# KMO_IO_MV2_4.net
KiCad netlist of a schematic drawn in EAGLE
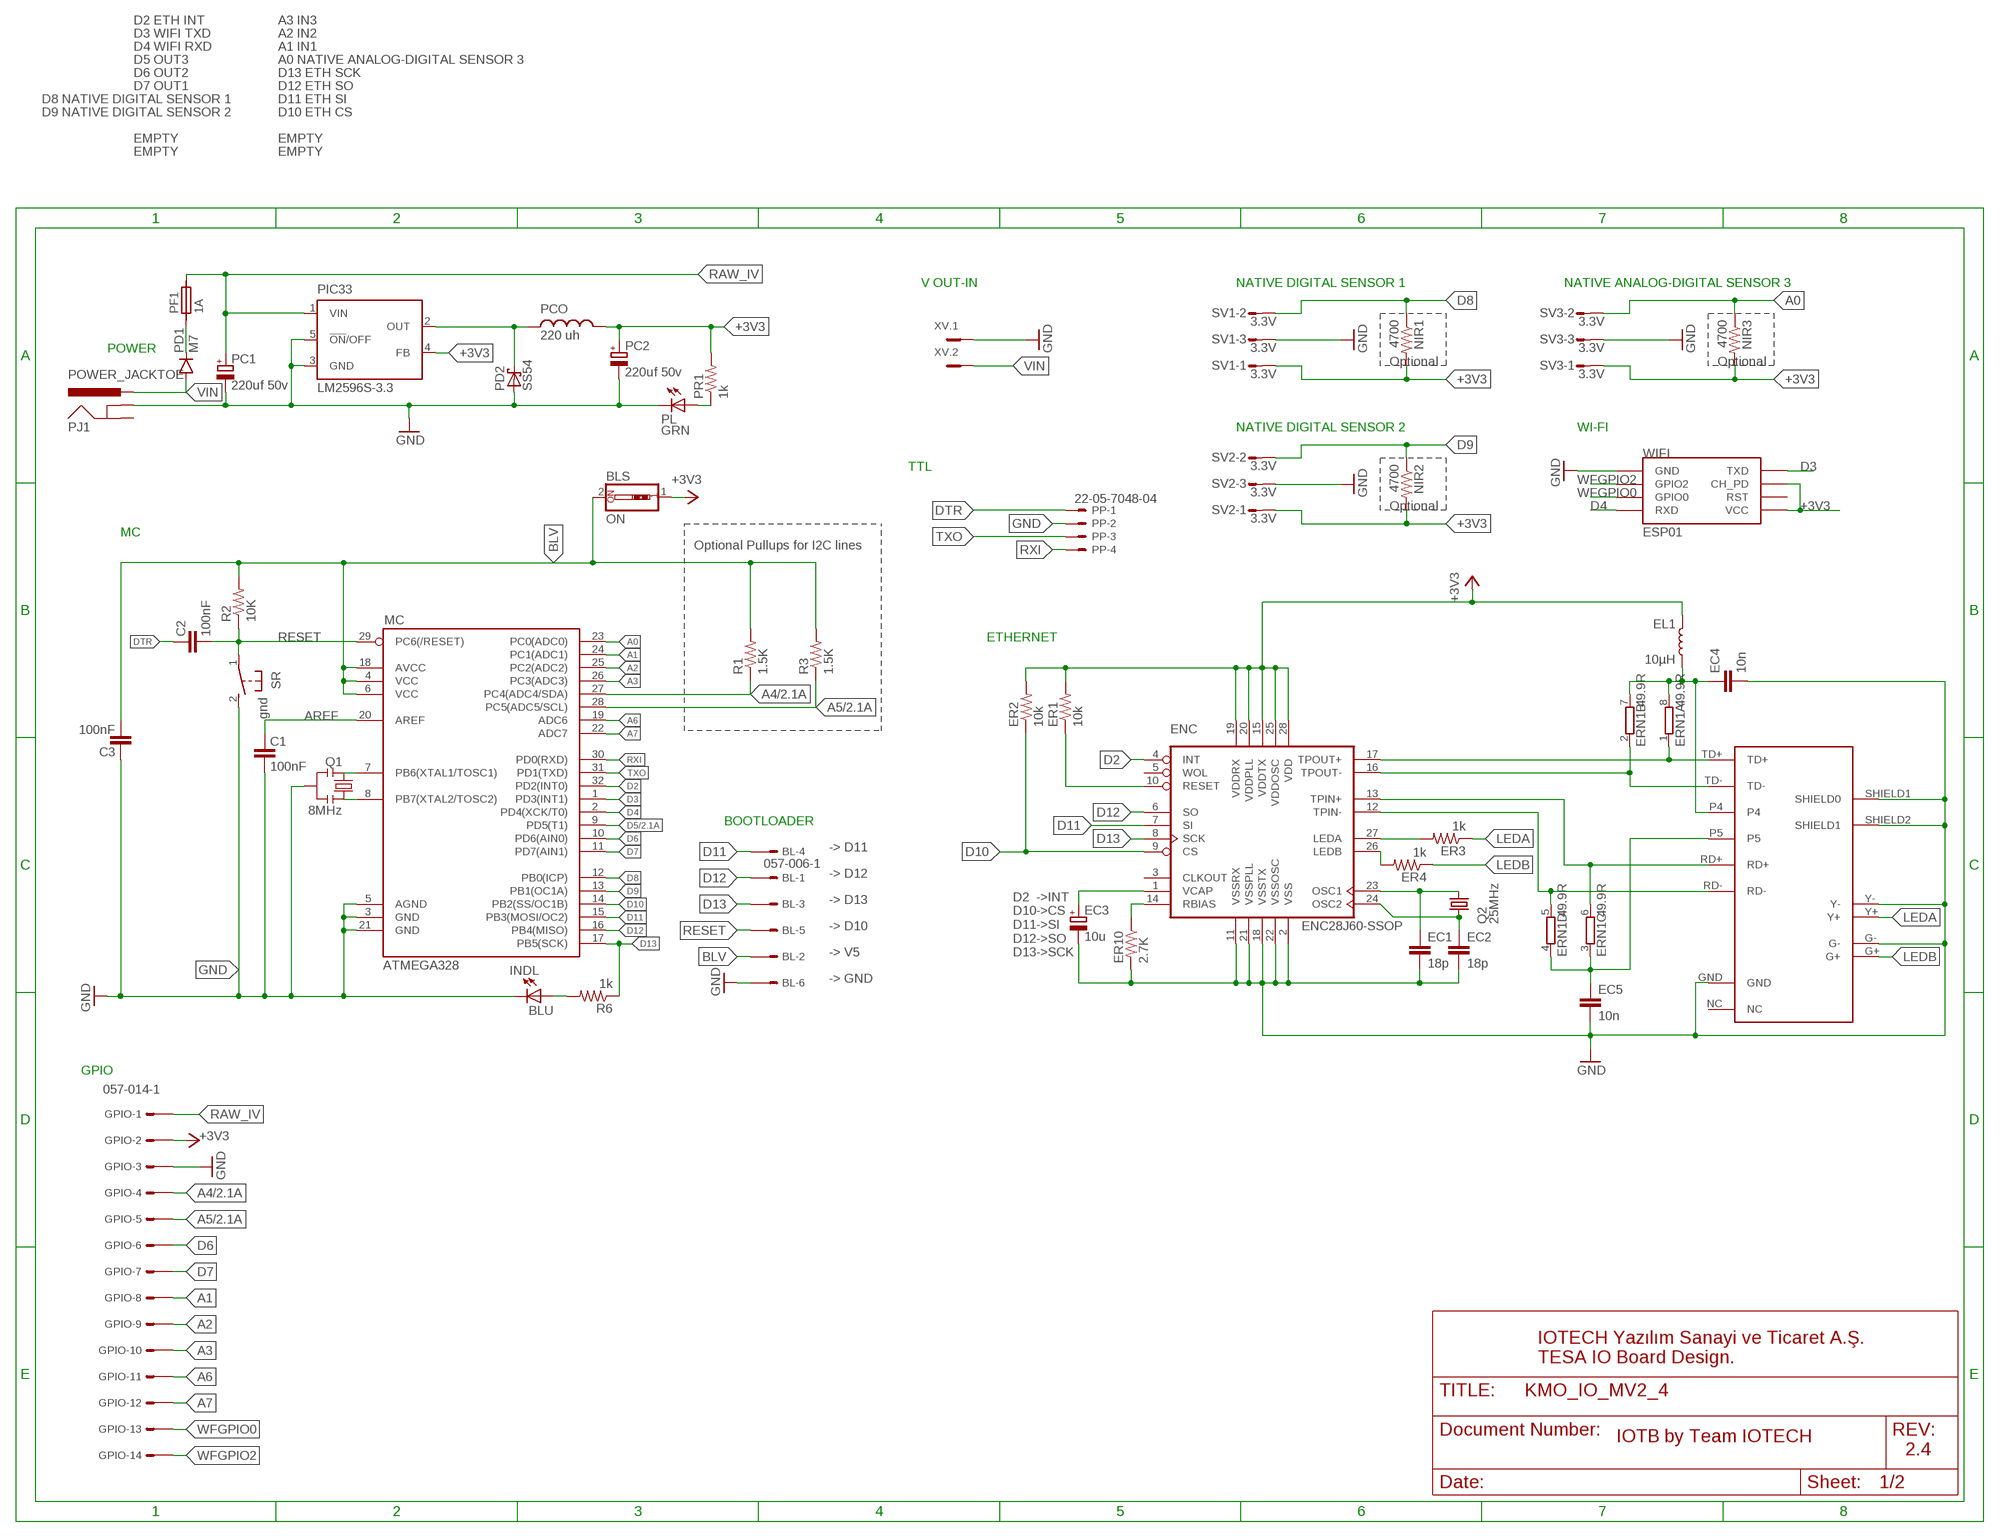
[diagram p0: schematic, sheet 1]
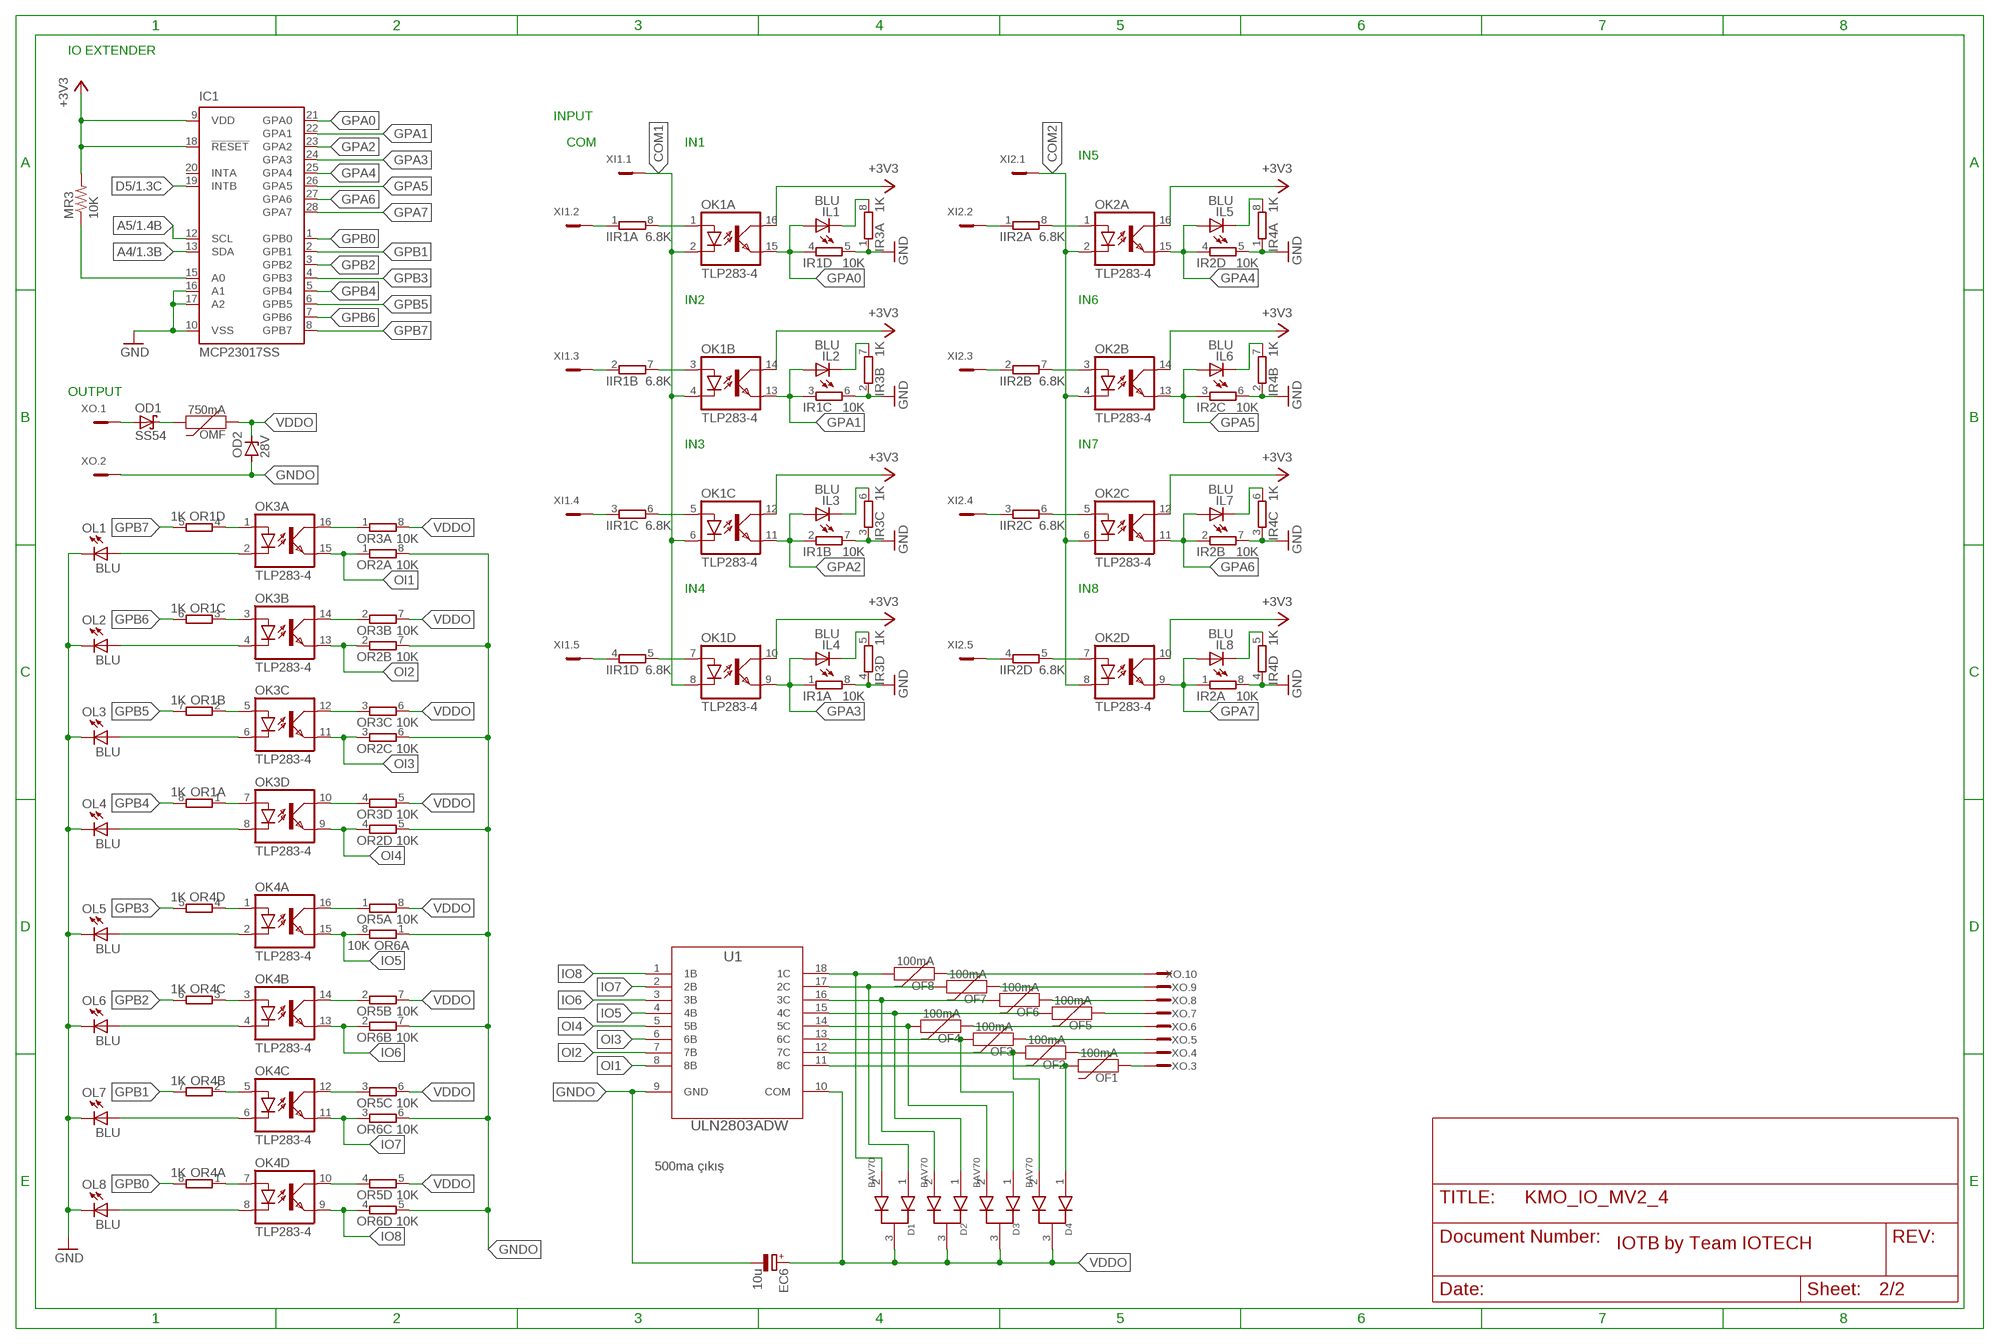
[diagram p1: schematic, sheet 2]

(export (version "E")
  (design (tool "Eeschema 10.0.6"))
  (components
    (comp (ref "BL")
      (value "057-006-1")
      (footprint "eagle-import:057-006-1")
      (libsource (lib "eagle-import") (part "057-006-1"))
    )
    (comp (ref "BLS")
      (value "ON")
      (footprint "eagle-import:EDG-01")
      (libsource (lib "eagle-import") (part "SW_DIP-1"))
    )
    (comp (ref "C1")
      (value "100nF")
      (footprint "eagle-import:0805")
      (libsource (lib "eagle-import") (part "CAP0805"))
    )
    (comp (ref "C2")
      (value "100nF")
      (footprint "eagle-import:0805")
      (libsource (lib "eagle-import") (part "CAP0805"))
    )
    (comp (ref "C3")
      (value "100nF")
      (footprint "eagle-import:0805")
      (libsource (lib "eagle-import") (part "CAP0805"))
    )
    (comp (ref "EC1")
      (value "18p")
      (footprint "eagle-import:0805")
      (libsource (lib "eagle-import") (part "CAP0805"))
    )
    (comp (ref "EC2")
      (value "18p")
      (footprint "eagle-import:0805")
      (libsource (lib "eagle-import") (part "CAP0805"))
    )
    (comp (ref "EC3")
      (value "10u")
      (footprint "eagle-import:CT3216")
      (libsource (lib "eagle-import") (part "CPOL-EUCT3216"))
    )
    (comp (ref "EC4")
      (value "10n")
      (footprint "eagle-import:0805")
      (libsource (lib "eagle-import") (part "CAP0805"))
    )
    (comp (ref "EC5")
      (value "10n")
      (footprint "eagle-import:0805")
      (libsource (lib "eagle-import") (part "CAP0805"))
    )
    (comp (ref "EL1")
      (value "10µH")
      (footprint "eagle-import:0805")
      (libsource (lib "eagle-import") (part "INDUCTOR-0805-3.3UH"))
    )
    (comp (ref "ENC")
      (value "ENC28J60-SSOP")
      (footprint "eagle-import:SSOP28")
      (libsource (lib "eagle-import") (part "ENC28J60-SSOP"))
    )
    (comp (ref "ER1")
      (value "10k")
      (footprint "eagle-import:0805")
      (libsource (lib "eagle-import") (part "RESISTOR0805-RES"))
    )
    (comp (ref "ER2")
      (value "10k")
      (footprint "eagle-import:0805")
      (libsource (lib "eagle-import") (part "RESISTOR0805-RES"))
    )
    (comp (ref "ER3")
      (value "1k")
      (footprint "eagle-import:0805")
      (libsource (lib "eagle-import") (part "RESISTOR0805-RES"))
    )
    (comp (ref "ER4")
      (value "1k")
      (footprint "eagle-import:0805")
      (libsource (lib "eagle-import") (part "RESISTOR0805-RES"))
    )
    (comp (ref "ER10")
      (value "2.7K")
      (footprint "eagle-import:0805")
      (libsource (lib "eagle-import") (part "RESISTOR0805-RES"))
    )
    (comp (ref "ERN1")
      (value "49.9R")
      (footprint "eagle-import:0603-ARV")
      (libsource (lib "eagle-import") (part "4R-N0603-ARV"))
    )
    (comp (ref "GPIO")
      (value "057-014-1")
      (footprint "eagle-import:057-014-1")
      (libsource (lib "eagle-import") (part "057-014-1"))
    )
    (comp (ref "INDL")
      (value "BLU")
      (footprint "eagle-import:CHIP-LED0805")
      (libsource (lib "eagle-import") (part "LEDCHIP-LED0805"))
    )
    (comp (ref "MC")
      (value "ATMEGA328")
      (footprint "eagle-import:TQFP32-08")
      (libsource (lib "eagle-import") (part "ATMEGA168"))
    )
    (comp (ref "NIR1")
      (value "4700")
      (footprint "eagle-import:0805")
      (libsource (lib "eagle-import") (part "RESISTOR0805-RES"))
    )
    (comp (ref "NIR2")
      (value "4700")
      (footprint "eagle-import:0805")
      (libsource (lib "eagle-import") (part "RESISTOR0805-RES"))
    )
    (comp (ref "NIR3")
      (value "4700")
      (footprint "eagle-import:0805")
      (libsource (lib "eagle-import") (part "RESISTOR0805-RES"))
    )
    (comp (ref "PC1")
      (value "220uf 50v")
      (footprint "eagle-import:140CLH-1010")
      (libsource (lib "eagle-import") (part "CPOL-EU140CLH-1010"))
    )
    (comp (ref "PC2")
      (value "220uf 50v")
      (footprint "eagle-import:140CLH-1010")
      (libsource (lib "eagle-import") (part "CPOL-EU140CLH-1010"))
    )
    (comp (ref "PCO")
      (value "220 uh")
      (footprint "eagle-import:MSS1260")
      (libsource (lib "eagle-import") (part "MSS1260"))
    )
    (comp (ref "PD1")
      (value "M7")
      (footprint "eagle-import:SMA-DIODE")
      (libsource (lib "eagle-import") (part "DIODESMA"))
    )
    (comp (ref "PD2")
      (value "SS54")
      (footprint "eagle-import:SMB")
      (libsource (lib "eagle-import") (part "SCHOTTKY-DIODESMD"))
    )
    (comp (ref "PF1")
      (value "1A")
      (footprint "eagle-import:1820")
      (libsource (lib "eagle-import") (part "SIBA194600"))
    )
    (comp (ref "PIC33")
      (value "LM2596S-3.3")
      (footprint "eagle-import:TO263-5")
      (fields
        (field (name "MF") "NATIONAL SEMICONDUCTOR")
        (field (name "MPN") "LM2596S-ADJ/NOPB")
        (field (name "SPICEPREFIX") "X")
      )
      (libsource (lib "eagle-import") (part "LM2596S"))
    )
    (comp (ref "PJ1")
      (value "POWER_JACKTOE")
      (footprint "eagle-import:POWER_JACK_SMD_OVERPASTE_TOE")
      (libsource (lib "eagle-import") (part "POWER_JACKTOE"))
    )
    (comp (ref "PL")
      (value "GRN")
      (footprint "eagle-import:CHIP-LED0805")
      (libsource (lib "eagle-import") (part "LEDCHIP-LED0805"))
    )
    (comp (ref "PP")
      (value "22-05-7048-04")
      (footprint "eagle-import:7395-04")
      (fields (field (name "MF") "MOLEX"))
      (libsource (lib "eagle-import") (part "22-?-0405-7048"))
    )
    (comp (ref "PR1")
      (value "1k")
      (footprint "eagle-import:0805")
      (libsource (lib "eagle-import") (part "RESISTOR0805-RES"))
    )
    (comp (ref "Q1")
      (value "8MHz")
      (footprint "eagle-import:RESONATOR-SMD-1_1")
      (libsource (lib "eagle-import") (part "RESONATOR1{colon}1"))
    )
    (comp (ref "Q2")
      (value "25MHz")
      (footprint "eagle-import:5.0X3.2_2")
      (libsource (lib "eagle-import") (part "KX-9B"))
    )
    (comp (ref "R1")
      (value "1.5K")
      (footprint "eagle-import:0805")
      (libsource (lib "eagle-import") (part "RESISTOR0805-RES"))
    )
    (comp (ref "R2")
      (value "10K")
      (footprint "eagle-import:0805")
      (libsource (lib "eagle-import") (part "RESISTOR0805-RES"))
    )
    (comp (ref "R3")
      (value "1.5K")
      (footprint "eagle-import:0805")
      (libsource (lib "eagle-import") (part "RESISTOR0805-RES"))
    )
    (comp (ref "R6")
      (value "1k")
      (footprint "eagle-import:0805")
      (libsource (lib "eagle-import") (part "RESISTOR0805-RES"))
    )
    (comp (ref "SR")
      (value "gnd")
      (footprint "eagle-import:B3F-31XX")
      (fields (field (name "MPN") "B3F-3100"))
      (libsource (lib "eagle-import") (part "31-XX"))
    )
    (comp (ref "SV1")
      (value "3.3V")
      (footprint "eagle-import:S03P")
      (libsource (lib "eagle-import") (part "S03P"))
    )
    (comp (ref "SV2")
      (value "3.3V")
      (footprint "eagle-import:S03P")
      (libsource (lib "eagle-import") (part "S03P"))
    )
    (comp (ref "SV3")
      (value "3.3V")
      (footprint "eagle-import:S03P")
      (libsource (lib "eagle-import") (part "S03P"))
    )
    (comp (ref "U$2")
      (value "HR911105A")
      (footprint "eagle-import:RJ45")
      (libsource (lib "eagle-import") (part "HR911105A"))
    )
    (comp (ref "WIFI")
      (value "ESP01")
      (footprint "eagle-import:ESP01")
      (libsource (lib "eagle-import") (part "ESP01"))
    )
    (comp (ref "XV")
      (value "MC2")
      (footprint "eagle-import:MC2")
      (libsource (lib "eagle-import") (part "MC2"))
    )
    (comp (ref "D1")
      (value "BAV70")
      (footprint "eagle-import:SOT-23-3")
      (fields (field (name "MF") "Multicomp") (field (name "MP") "BAV70+"))
      (libsource (lib "eagle-import") (part "BAV70"))
    )
    (comp (ref "D2")
      (value "BAV70")
      (footprint "eagle-import:SOT-23-3")
      (fields (field (name "MF") "Multicomp") (field (name "MP") "BAV70+"))
      (libsource (lib "eagle-import") (part "BAV70"))
    )
    (comp (ref "D3")
      (value "BAV70")
      (footprint "eagle-import:SOT-23-3")
      (fields (field (name "MF") "Multicomp") (field (name "MP") "BAV70+"))
      (libsource (lib "eagle-import") (part "BAV70"))
    )
    (comp (ref "D4")
      (value "BAV70")
      (footprint "eagle-import:SOT-23-3")
      (fields (field (name "MF") "Multicomp") (field (name "MP") "BAV70+"))
      (libsource (lib "eagle-import") (part "BAV70"))
    )
    (comp (ref "EC6")
      (value "10u")
      (footprint "eagle-import:CT3216")
      (libsource (lib "eagle-import") (part "CPOL-EUCT3216"))
    )
    (comp (ref "IC1")
      (value "MCP23017SS")
      (footprint "eagle-import:SSOP28")
      (fields (field (name "MF") "MICROCHIP") (field (name "MPN") "MCP23017-E/SS"))
      (libsource (lib "eagle-import") (part "MCP23017SS"))
    )
    (comp (ref "IIR1")
      (value "6.8K")
      (footprint "eagle-import:0603-ARV")
      (libsource (lib "eagle-import") (part "4R-N0603-ARV"))
    )
    (comp (ref "IIR2")
      (value "6.8K")
      (footprint "eagle-import:0603-ARV")
      (libsource (lib "eagle-import") (part "4R-N0603-ARV"))
    )
    (comp (ref "IL1")
      (value "BLU")
      (footprint "eagle-import:CHIP-LED0805")
      (libsource (lib "eagle-import") (part "LEDCHIP-LED0805"))
    )
    (comp (ref "IL2")
      (value "BLU")
      (footprint "eagle-import:CHIP-LED0805")
      (libsource (lib "eagle-import") (part "LEDCHIP-LED0805"))
    )
    (comp (ref "IL3")
      (value "BLU")
      (footprint "eagle-import:CHIP-LED0805")
      (libsource (lib "eagle-import") (part "LEDCHIP-LED0805"))
    )
    (comp (ref "IL4")
      (value "BLU")
      (footprint "eagle-import:CHIP-LED0805")
      (libsource (lib "eagle-import") (part "LEDCHIP-LED0805"))
    )
    (comp (ref "IL5")
      (value "BLU")
      (footprint "eagle-import:CHIP-LED0805")
      (libsource (lib "eagle-import") (part "LEDCHIP-LED0805"))
    )
    (comp (ref "IL6")
      (value "BLU")
      (footprint "eagle-import:CHIP-LED0805")
      (libsource (lib "eagle-import") (part "LEDCHIP-LED0805"))
    )
    (comp (ref "IL7")
      (value "BLU")
      (footprint "eagle-import:CHIP-LED0805")
      (libsource (lib "eagle-import") (part "LEDCHIP-LED0805"))
    )
    (comp (ref "IL8")
      (value "BLU")
      (footprint "eagle-import:CHIP-LED0805")
      (libsource (lib "eagle-import") (part "LEDCHIP-LED0805"))
    )
    (comp (ref "IR1")
      (value "10K")
      (footprint "eagle-import:0603-ARV")
      (libsource (lib "eagle-import") (part "4R-N0603-ARV"))
    )
    (comp (ref "IR2")
      (value "10K")
      (footprint "eagle-import:0603-ARV")
      (libsource (lib "eagle-import") (part "4R-N0603-ARV"))
    )
    (comp (ref "IR3")
      (value "1K")
      (footprint "eagle-import:0603-ARV")
      (libsource (lib "eagle-import") (part "4R-N0603-ARV"))
    )
    (comp (ref "IR4")
      (value "1K")
      (footprint "eagle-import:0603-ARV")
      (libsource (lib "eagle-import") (part "4R-N0603-ARV"))
    )
    (comp (ref "MR3")
      (value "10K")
      (footprint "eagle-import:0805")
      (libsource (lib "eagle-import") (part "RESISTOR0805-RES"))
    )
    (comp (ref "OD1")
      (value "SS54")
      (footprint "eagle-import:SMB")
      (libsource (lib "eagle-import") (part "SCHOTTKY-DIODESMD"))
    )
    (comp (ref "OD2")
      (value "28V")
      (footprint "eagle-import:SMB")
      (libsource (lib "eagle-import") (part "ZENER-DIODESMB"))
    )
    (comp (ref "OF1")
      (value "100mA")
      (footprint "eagle-import:1206")
      (libsource (lib "eagle-import") (part "PPTC_0.75A"))
    )
    (comp (ref "OF2")
      (value "100mA")
      (footprint "eagle-import:1206")
      (libsource (lib "eagle-import") (part "PPTC_0.75A"))
    )
    (comp (ref "OF3")
      (value "100mA")
      (footprint "eagle-import:1206")
      (libsource (lib "eagle-import") (part "PPTC_0.75A"))
    )
    (comp (ref "OF4")
      (value "100mA")
      (footprint "eagle-import:1206")
      (libsource (lib "eagle-import") (part "PPTC_0.75A"))
    )
    (comp (ref "OF5")
      (value "100mA")
      (footprint "eagle-import:1206")
      (libsource (lib "eagle-import") (part "PPTC_0.75A"))
    )
    (comp (ref "OF6")
      (value "100mA")
      (footprint "eagle-import:1206")
      (libsource (lib "eagle-import") (part "PPTC_0.75A"))
    )
    (comp (ref "OF7")
      (value "100mA")
      (footprint "eagle-import:1206")
      (libsource (lib "eagle-import") (part "PPTC_0.75A"))
    )
    (comp (ref "OF8")
      (value "100mA")
      (footprint "eagle-import:1206")
      (libsource (lib "eagle-import") (part "PPTC_0.75A"))
    )
    (comp (ref "OK1")
      (value "TLP283-4")
      (footprint "eagle-import:MINI-FLAT-16")
      (fields (field (name "SPICEPREFIX") "O"))
      (libsource (lib "eagle-import") (part "TLP283-4"))
    )
    (comp (ref "OK2")
      (value "TLP283-4")
      (footprint "eagle-import:MINI-FLAT-16")
      (fields (field (name "SPICEPREFIX") "O"))
      (libsource (lib "eagle-import") (part "TLP283-4"))
    )
    (comp (ref "OK3")
      (value "TLP283-4")
      (footprint "eagle-import:MINI-FLAT-16")
      (libsource (lib "eagle-import") (part "TLP283-4"))
    )
    (comp (ref "OK4")
      (value "TLP283-4")
      (footprint "eagle-import:MINI-FLAT-16")
      (libsource (lib "eagle-import") (part "TLP283-4"))
    )
    (comp (ref "OL1")
      (value "BLU")
      (footprint "eagle-import:CHIP-LED0805")
      (libsource (lib "eagle-import") (part "LEDCHIP-LED0805"))
    )
    (comp (ref "OL2")
      (value "BLU")
      (footprint "eagle-import:CHIP-LED0805")
      (libsource (lib "eagle-import") (part "LEDCHIP-LED0805"))
    )
    (comp (ref "OL3")
      (value "BLU")
      (footprint "eagle-import:CHIP-LED0805")
      (libsource (lib "eagle-import") (part "LEDCHIP-LED0805"))
    )
    (comp (ref "OL4")
      (value "BLU")
      (footprint "eagle-import:CHIP-LED0805")
      (libsource (lib "eagle-import") (part "LEDCHIP-LED0805"))
    )
    (comp (ref "OL5")
      (value "BLU")
      (footprint "eagle-import:CHIP-LED0805")
      (libsource (lib "eagle-import") (part "LEDCHIP-LED0805"))
    )
    (comp (ref "OL6")
      (value "BLU")
      (footprint "eagle-import:CHIP-LED0805")
      (libsource (lib "eagle-import") (part "LEDCHIP-LED0805"))
    )
    (comp (ref "OL7")
      (value "BLU")
      (footprint "eagle-import:CHIP-LED0805")
      (libsource (lib "eagle-import") (part "LEDCHIP-LED0805"))
    )
    (comp (ref "OL8")
      (value "BLU")
      (footprint "eagle-import:CHIP-LED0805")
      (libsource (lib "eagle-import") (part "LEDCHIP-LED0805"))
    )
    (comp (ref "OMF")
      (value "750mA")
      (footprint "eagle-import:1206")
      (libsource (lib "eagle-import") (part "PPTC_0.75A"))
    )
    (comp (ref "OR1")
      (value "1K")
      (footprint "eagle-import:0603-ARV")
      (libsource (lib "eagle-import") (part "4R-N0603-ARV"))
    )
    (comp (ref "OR2")
      (value "10K")
      (footprint "eagle-import:0603-ARV")
      (libsource (lib "eagle-import") (part "4R-N0603-ARV"))
    )
    (comp (ref "OR3")
      (value "10K")
      (footprint "eagle-import:0603-ARV")
      (libsource (lib "eagle-import") (part "4R-N0603-ARV"))
    )
    (comp (ref "OR4")
      (value "1K")
      (footprint "eagle-import:0603-ARV")
      (libsource (lib "eagle-import") (part "4R-N0603-ARV"))
    )
    (comp (ref "OR5")
      (value "10K")
      (footprint "eagle-import:0603-ARV")
      (libsource (lib "eagle-import") (part "4R-N0603-ARV"))
    )
    (comp (ref "OR6")
      (value "10K")
      (footprint "eagle-import:0603-ARV")
      (libsource (lib "eagle-import") (part "4R-N0603-ARV"))
    )
    (comp (ref "U1")
      (value "ULN2803ADW")
      (footprint "eagle-import:SOIC127P1030X265-18N")
      (libsource (lib "eagle-import") (part "ULN2803ADW"))
    )
    (comp (ref "XI1")
      (value "MC5")
      (footprint "eagle-import:MC5")
      (libsource (lib "eagle-import") (part "MC5"))
    )
    (comp (ref "XI2")
      (value "MC5")
      (footprint "eagle-import:MC5")
      (libsource (lib "eagle-import") (part "MC5"))
    )
    (comp (ref "XO")
      (value "MC10")
      (footprint "eagle-import:MC10")
      (libsource (lib "eagle-import") (part "MC10"))
    )
  )
  (nets
    (net (code "1") (name "+3V3") (class "Default")
      (node (ref "BLS") (pin "1") (pinfunction "1_1") (pintype "passive"))
      (node (ref "EL1") (pin "1") (pinfunction "1_1") (pintype "passive"))
      (node (ref "ENC") (pin "15") (pinfunction "VDDTX_15") (pintype "power_in"))
      (node (ref "ENC") (pin "19") (pinfunction "VDDRX_19") (pintype "power_in"))
      (node (ref "ENC") (pin "20") (pinfunction "VDDPLL_20") (pintype "power_in"))
      (node (ref "ENC") (pin "25") (pinfunction "VDDOSC_25") (pintype "power_in"))
      (node (ref "ENC") (pin "28") (pinfunction "VDD_28") (pintype "power_in"))
      (node (ref "ER1") (pin "2") (pinfunction "2_2") (pintype "passive"))
      (node (ref "ER2") (pin "2") (pinfunction "2_2") (pintype "passive"))
      (node (ref "GPIO") (pin "2") (pinfunction "S_2") (pintype "passive"))
      (node (ref "IC1") (pin "18") (pinfunction "~{RESET}_18") (pintype "input"))
      (node (ref "IC1") (pin "9") (pinfunction "VDD_9") (pintype "power_in"))
      (node (ref "MR3") (pin "2") (pinfunction "2_2") (pintype "passive"))
      (node (ref "NIR1") (pin "2") (pinfunction "2_2") (pintype "passive"))
      (node (ref "NIR2") (pin "2") (pinfunction "2_2") (pintype "passive"))
      (node (ref "NIR3") (pin "2") (pinfunction "2_2") (pintype "passive"))
      (node (ref "OK1") (pin "10") (pinfunction "COL_10") (pintype "passive"))
      (node (ref "OK1") (pin "12") (pinfunction "COL_12") (pintype "passive"))
      (node (ref "OK1") (pin "14") (pinfunction "COL_14") (pintype "passive"))
      (node (ref "OK1") (pin "16") (pinfunction "COL_16") (pintype "passive"))
      (node (ref "OK2") (pin "10") (pinfunction "COL_10") (pintype "passive"))
      (node (ref "OK2") (pin "12") (pinfunction "COL_12") (pintype "passive"))
      (node (ref "OK2") (pin "14") (pinfunction "COL_14") (pintype "passive"))
      (node (ref "OK2") (pin "16") (pinfunction "COL_16") (pintype "passive"))
      (node (ref "PC2") (pin "+") (pinfunction "+_+") (pintype "passive"))
      (node (ref "PCO") (pin "P$1") (pinfunction "P$1_P$1") (pintype "passive"))
      (node (ref "PIC33") (pin "4") (pinfunction "FB_4") (pintype "input"))
      (node (ref "PR1") (pin "2") (pinfunction "2_2") (pintype "passive"))
      (node (ref "SV1") (pin "1") (pinfunction "S_1") (pintype "passive"))
      (node (ref "SV2") (pin "1") (pinfunction "S_1") (pintype "passive"))
      (node (ref "SV3") (pin "1") (pinfunction "S_1") (pintype "passive"))
      (node (ref "WIFI") (pin "CH_PD") (pinfunction "CH_PD_CH_PD") (pintype "bidirectional"))
      (node (ref "WIFI") (pin "VCC") (pinfunction "VCC_VCC") (pintype "bidirectional"))
    )
    (net (code "2") (name "A0") (class "Default")
      (node (ref "MC") (pin "23") (pinfunction "PC0(ADC0)_23") (pintype "bidirectional"))
      (node (ref "NIR3") (pin "1") (pinfunction "1_1") (pintype "passive"))
      (node (ref "SV3") (pin "2") (pinfunction "S_2") (pintype "passive"))
    )
    (net (code "3") (name "A1") (class "Default")
      (node (ref "GPIO") (pin "8") (pinfunction "S_8") (pintype "passive"))
      (node (ref "MC") (pin "24") (pinfunction "PC1(ADC1)_24") (pintype "bidirectional"))
    )
    (net (code "4") (name "A2") (class "Default")
      (node (ref "GPIO") (pin "9") (pinfunction "S_9") (pintype "passive"))
      (node (ref "MC") (pin "25") (pinfunction "PC2(ADC2)_25") (pintype "bidirectional"))
    )
    (net (code "5") (name "A3") (class "Default")
      (node (ref "GPIO") (pin "10") (pinfunction "S_10") (pintype "passive"))
      (node (ref "MC") (pin "26") (pinfunction "PC3(ADC3)_26") (pintype "bidirectional"))
    )
    (net (code "6") (name "A4") (class "Default")
      (node (ref "GPIO") (pin "4") (pinfunction "S_4") (pintype "passive"))
      (node (ref "IC1") (pin "13") (pinfunction "SDA_13") (pintype "bidirectional"))
      (node (ref "MC") (pin "27") (pinfunction "PC4(ADC4/SDA)_27") (pintype "bidirectional"))
      (node (ref "R1") (pin "1") (pinfunction "1_1") (pintype "passive"))
    )
    (net (code "7") (name "A5") (class "Default")
      (node (ref "GPIO") (pin "5") (pinfunction "S_5") (pintype "passive"))
      (node (ref "IC1") (pin "12") (pinfunction "SCL_12") (pintype "input"))
      (node (ref "MC") (pin "28") (pinfunction "PC5(ADC5/SCL)_28") (pintype "bidirectional"))
      (node (ref "R3") (pin "1") (pinfunction "1_1") (pintype "passive"))
    )
    (net (code "8") (name "A6") (class "Default")
      (node (ref "GPIO") (pin "11") (pinfunction "S_11") (pintype "passive"))
      (node (ref "MC") (pin "19") (pinfunction "ADC6_19") (pintype "bidirectional"))
    )
    (net (code "9") (name "A7") (class "Default")
      (node (ref "GPIO") (pin "12") (pinfunction "S_12") (pintype "passive"))
      (node (ref "MC") (pin "22") (pinfunction "ADC7_22") (pintype "bidirectional"))
    )
    (net (code "10") (name "AREF") (class "Default")
      (node (ref "C1") (pin "2") (pinfunction "2_2") (pintype "passive"))
      (node (ref "MC") (pin "20") (pinfunction "AREF_20") (pintype "bidirectional"))
    )
    (net (code "11") (name "BLV") (class "Default")
      (node (ref "BL") (pin "2") (pinfunction "S_2") (pintype "passive"))
      (node (ref "BLS") (pin "2") (pinfunction "2_2") (pintype "passive"))
      (node (ref "C3") (pin "1") (pinfunction "1_1") (pintype "passive"))
      (node (ref "MC") (pin "18") (pinfunction "AVCC_18") (pintype "bidirectional"))
      (node (ref "MC") (pin "4") (pinfunction "VCC_4") (pintype "bidirectional"))
      (node (ref "MC") (pin "6") (pinfunction "VCC_6") (pintype "bidirectional"))
      (node (ref "R1") (pin "2") (pinfunction "2_2") (pintype "passive"))
      (node (ref "R2") (pin "2") (pinfunction "2_2") (pintype "passive"))
      (node (ref "R3") (pin "2") (pinfunction "2_2") (pintype "passive"))
    )
    (net (code "12") (name "COM1") (class "Default")
      (node (ref "OK1") (pin "2") (pinfunction "C_2") (pintype "passive"))
      (node (ref "OK1") (pin "4") (pinfunction "C_4") (pintype "passive"))
      (node (ref "OK1") (pin "6") (pinfunction "C_6") (pintype "passive"))
      (node (ref "OK1") (pin "8") (pinfunction "C_8") (pintype "passive"))
      (node (ref "XI1") (pin "1") (pinfunction "SK_1") (pintype "passive"))
    )
    (net (code "13") (name "COM2") (class "Default")
      (node (ref "OK2") (pin "2") (pinfunction "C_2") (pintype "passive"))
      (node (ref "OK2") (pin "4") (pinfunction "C_4") (pintype "passive"))
      (node (ref "OK2") (pin "6") (pinfunction "C_6") (pintype "passive"))
      (node (ref "OK2") (pin "8") (pinfunction "C_8") (pintype "passive"))
      (node (ref "XI2") (pin "1") (pinfunction "SK_1") (pintype "passive"))
    )
    (net (code "14") (name "D2") (class "Default")
      (node (ref "ENC") (pin "4") (pinfunction "INT_4") (pintype "output"))
      (node (ref "MC") (pin "32") (pinfunction "PD2(INT0)_32") (pintype "bidirectional"))
    )
    (net (code "15") (name "D3") (class "Default")
      (node (ref "MC") (pin "1") (pinfunction "PD3(INT1)_1") (pintype "bidirectional"))
      (node (ref "WIFI") (pin "TX") (pinfunction "TXD_TX") (pintype "bidirectional"))
    )
    (net (code "16") (name "D4") (class "Default")
      (node (ref "MC") (pin "2") (pinfunction "PD4(XCK/T0)_2") (pintype "bidirectional"))
      (node (ref "WIFI") (pin "RX") (pinfunction "RXD_RX") (pintype "bidirectional"))
    )
    (net (code "17") (name "D5") (class "Default")
      (node (ref "IC1") (pin "19") (pinfunction "INTB_19") (pintype "output"))
      (node (ref "MC") (pin "9") (pinfunction "PD5(T1)_9") (pintype "bidirectional"))
    )
    (net (code "18") (name "D6") (class "Default")
      (node (ref "GPIO") (pin "6") (pinfunction "S_6") (pintype "passive"))
      (node (ref "MC") (pin "10") (pinfunction "PD6(AIN0)_10") (pintype "bidirectional"))
    )
    (net (code "19") (name "D7") (class "Default")
      (node (ref "GPIO") (pin "7") (pinfunction "S_7") (pintype "passive"))
      (node (ref "MC") (pin "11") (pinfunction "PD7(AIN1)_11") (pintype "bidirectional"))
    )
    (net (code "20") (name "D8") (class "Default")
      (node (ref "MC") (pin "12") (pinfunction "PB0(ICP)_12") (pintype "bidirectional"))
      (node (ref "NIR1") (pin "1") (pinfunction "1_1") (pintype "passive"))
      (node (ref "SV1") (pin "2") (pinfunction "S_2") (pintype "passive"))
    )
    (net (code "21") (name "D9") (class "Default")
      (node (ref "MC") (pin "13") (pinfunction "PB1(OC1A)_13") (pintype "bidirectional"))
      (node (ref "NIR2") (pin "1") (pinfunction "1_1") (pintype "passive"))
      (node (ref "SV2") (pin "2") (pinfunction "S_2") (pintype "passive"))
    )
    (net (code "22") (name "D10") (class "Default")
      (node (ref "ENC") (pin "9") (pinfunction "CS_9") (pintype "input"))
      (node (ref "ER2") (pin "1") (pinfunction "1_1") (pintype "passive"))
      (node (ref "MC") (pin "14") (pinfunction "PB2(SS/OC1B)_14") (pintype "bidirectional"))
    )
    (net (code "23") (name "D11") (class "Default")
      (node (ref "BL") (pin "4") (pinfunction "S_4") (pintype "passive"))
      (node (ref "ENC") (pin "7") (pinfunction "SI_7") (pintype "input"))
      (node (ref "MC") (pin "15") (pinfunction "PB3(MOSI/OC2)_15") (pintype "bidirectional"))
    )
    (net (code "24") (name "D12") (class "Default")
      (node (ref "BL") (pin "1") (pinfunction "S_1") (pintype "passive"))
      (node (ref "ENC") (pin "6") (pinfunction "SO_6") (pintype "output"))
      (node (ref "MC") (pin "16") (pinfunction "PB4(MISO)_16") (pintype "bidirectional"))
    )
    (net (code "25") (name "D13") (class "Default")
      (node (ref "BL") (pin "3") (pinfunction "S_3") (pintype "passive"))
      (node (ref "ENC") (pin "8") (pinfunction "SCK_8") (pintype "input"))
      (node (ref "MC") (pin "17") (pinfunction "PB5(SCK)_17") (pintype "bidirectional"))
      (node (ref "R6") (pin "1") (pinfunction "1_1") (pintype "passive"))
    )
    (net (code "26") (name "DTR") (class "Default")
      (node (ref "C2") (pin "2") (pinfunction "2_2") (pintype "passive"))
      (node (ref "PP") (pin "1") (pinfunction "S_1") (pintype "passive"))
    )
    (net (code "27") (name "GND") (class "Default")
      (node (ref "BL") (pin "6") (pinfunction "S_6") (pintype "passive"))
      (node (ref "C1") (pin "1") (pinfunction "1_1") (pintype "passive"))
      (node (ref "C3") (pin "2") (pinfunction "2_2") (pintype "passive"))
      (node (ref "EC1") (pin "2") (pinfunction "2_2") (pintype "passive"))
      (node (ref "EC2") (pin "2") (pinfunction "2_2") (pintype "passive"))
      (node (ref "EC3") (pin "-") (pinfunction "-_-") (pintype "passive"))
      (node (ref "EC4") (pin "2") (pinfunction "2_2") (pintype "passive"))
      (node (ref "EC5") (pin "2") (pinfunction "2_2") (pintype "passive"))
      (node (ref "ENC") (pin "11") (pinfunction "VSSRX_11") (pintype "power_in"))
      (node (ref "ENC") (pin "18") (pinfunction "VSSTX_18") (pintype "power_in"))
      (node (ref "ENC") (pin "2") (pinfunction "VSS_2") (pintype "power_in"))
      (node (ref "ENC") (pin "21") (pinfunction "VSSPLL_21") (pintype "power_in"))
      (node (ref "ENC") (pin "22") (pinfunction "VSSOSC_22") (pintype "power_in"))
      (node (ref "ER10") (pin "2") (pinfunction "2_2") (pintype "passive"))
      (node (ref "GPIO") (pin "3") (pinfunction "S_3") (pintype "passive"))
      (node (ref "IC1") (pin "10") (pinfunction "VSS_10") (pintype "power_in"))
      (node (ref "IC1") (pin "16") (pinfunction "A1_16") (pintype "input"))
      (node (ref "IC1") (pin "17") (pinfunction "A2_17") (pintype "input"))
      (node (ref "INDL") (pin "C") (pinfunction "C_C") (pintype "passive"))
      (node (ref "IR1") (pin "5") (pinfunction "2_5") (pintype "passive"))
      (node (ref "IR1") (pin "6") (pinfunction "2_6") (pintype "passive"))
      (node (ref "IR1") (pin "7") (pinfunction "2_7") (pintype "passive"))
      (node (ref "IR1") (pin "8") (pinfunction "2_8") (pintype "passive"))
      (node (ref "IR2") (pin "5") (pinfunction "2_5") (pintype "passive"))
      (node (ref "IR2") (pin "6") (pinfunction "2_6") (pintype "passive"))
      (node (ref "IR2") (pin "7") (pinfunction "2_7") (pintype "passive"))
      (node (ref "IR2") (pin "8") (pinfunction "2_8") (pintype "passive"))
      (node (ref "IR3") (pin "1") (pinfunction "1_1") (pintype "passive"))
      (node (ref "IR3") (pin "2") (pinfunction "1_2") (pintype "passive"))
      (node (ref "IR3") (pin "3") (pinfunction "1_3") (pintype "passive"))
      (node (ref "IR3") (pin "4") (pinfunction "1_4") (pintype "passive"))
      (node (ref "IR4") (pin "1") (pinfunction "1_1") (pintype "passive"))
      (node (ref "IR4") (pin "2") (pinfunction "1_2") (pintype "passive"))
      (node (ref "IR4") (pin "3") (pinfunction "1_3") (pintype "passive"))
      (node (ref "IR4") (pin "4") (pinfunction "1_4") (pintype "passive"))
      (node (ref "MC") (pin "21") (pinfunction "GND_21") (pintype "bidirectional"))
      (node (ref "MC") (pin "3") (pinfunction "GND_3") (pintype "bidirectional"))
      (node (ref "MC") (pin "5") (pinfunction "AGND_5") (pintype "bidirectional"))
      (node (ref "OL1") (pin "C") (pinfunction "C_C") (pintype "passive"))
      (node (ref "OL2") (pin "C") (pinfunction "C_C") (pintype "passive"))
      (node (ref "OL3") (pin "C") (pinfunction "C_C") (pintype "passive"))
      (node (ref "OL4") (pin "C") (pinfunction "C_C") (pintype "passive"))
      (node (ref "OL5") (pin "C") (pinfunction "C_C") (pintype "passive"))
      (node (ref "OL6") (pin "C") (pinfunction "C_C") (pintype "passive"))
      (node (ref "OL7") (pin "C") (pinfunction "C_C") (pintype "passive"))
      (node (ref "OL8") (pin "C") (pinfunction "C_C") (pintype "passive"))
      (node (ref "PC1") (pin "-") (pinfunction "-_-") (pintype "passive"))
      (node (ref "PC2") (pin "-") (pinfunction "-_-") (pintype "passive"))
      (node (ref "PD2") (pin "A") (pinfunction "A_A") (pintype "passive"))
      (node (ref "PIC33") (pin "3") (pinfunction "GND_3") (pintype "power_in"))
      (node (ref "PIC33") (pin "5") (pinfunction "~{ON}/OFF_5") (pintype "input"))
      (node (ref "PJ1") (pin "GND") (pinfunction "GNDBREAK_GND") (pintype "bidirectional"))
      (node (ref "PL") (pin "C") (pinfunction "C_C") (pintype "passive"))
      (node (ref "PP") (pin "2") (pinfunction "S_2") (pintype "passive"))
      (node (ref "Q1") (pin "2") (pinfunction "2_2") (pintype "passive"))
      (node (ref "SR") (pin "2") (pinfunction "S_2") (pintype "passive"))
      (node (ref "SV1") (pin "3") (pinfunction "S_3") (pintype "passive"))
      (node (ref "SV2") (pin "3") (pinfunction "S_3") (pintype "passive"))
      (node (ref "SV3") (pin "3") (pinfunction "S_3") (pintype "passive"))
      (node (ref "U$2") (pin "G-") (pinfunction "G-_G-") (pintype "bidirectional"))
      (node (ref "U$2") (pin "GND") (pinfunction "GND_GND") (pintype "bidirectional"))
      (node (ref "U$2") (pin "SHIELD1") (pinfunction "SHIELD0_SHIELD1") (pintype "bidirectional"))
      (node (ref "U$2") (pin "SHIELD2") (pinfunction "SHIELD1_SHIELD2") (pintype "bidirectional"))
      (node (ref "U$2") (pin "Y-") (pinfunction "Y-_Y-") (pintype "bidirectional"))
      (node (ref "WIFI") (pin "GND") (pinfunction "GND_GND") (pintype "bidirectional"))
      (node (ref "XV") (pin "1") (pinfunction "SK_1") (pintype "passive"))
    )
    (net (code "28") (name "GNDO") (class "Default")
      (node (ref "EC6") (pin "-") (pinfunction "-_-") (pintype "passive"))
      (node (ref "OD2") (pin "A") (pinfunction "A_A") (pintype "passive"))
      (node (ref "OR2") (pin "5") (pinfunction "2_5") (pintype "passive"))
      (node (ref "OR2") (pin "6") (pinfunction "2_6") (pintype "passive"))
      (node (ref "OR2") (pin "7") (pinfunction "2_7") (pintype "passive"))
      (node (ref "OR2") (pin "8") (pinfunction "2_8") (pintype "passive"))
      (node (ref "OR6") (pin "1") (pinfunction "1_1") (pintype "passive"))
      (node (ref "OR6") (pin "5") (pinfunction "2_5") (pintype "passive"))
      (node (ref "OR6") (pin "6") (pinfunction "2_6") (pintype "passive"))
      (node (ref "OR6") (pin "7") (pinfunction "2_7") (pintype "passive"))
      (node (ref "U1") (pin "9") (pinfunction "GND_9") (pintype "passive"))
      (node (ref "XO") (pin "2") (pinfunction "SK_2") (pintype "passive"))
    )
    (net (code "29") (name "GPA0") (class "Default")
      (node (ref "IC1") (pin "21") (pinfunction "GPA0_21") (pintype "bidirectional"))
      (node (ref "IL1") (pin "A") (pinfunction "A_A") (pintype "passive"))
      (node (ref "IR1") (pin "4") (pinfunction "1_4") (pintype "passive"))
      (node (ref "OK1") (pin "15") (pinfunction "EMIT_15") (pintype "passive"))
    )
    (net (code "30") (name "GPA1") (class "Default")
      (node (ref "IC1") (pin "22") (pinfunction "GPA1_22") (pintype "bidirectional"))
      (node (ref "IL2") (pin "A") (pinfunction "A_A") (pintype "passive"))
      (node (ref "IR1") (pin "3") (pinfunction "1_3") (pintype "passive"))
      (node (ref "OK1") (pin "13") (pinfunction "EMIT_13") (pintype "passive"))
    )
    (net (code "31") (name "GPA2") (class "Default")
      (node (ref "IC1") (pin "23") (pinfunction "GPA2_23") (pintype "bidirectional"))
      (node (ref "IL3") (pin "A") (pinfunction "A_A") (pintype "passive"))
      (node (ref "IR1") (pin "2") (pinfunction "1_2") (pintype "passive"))
      (node (ref "OK1") (pin "11") (pinfunction "EMIT_11") (pintype "passive"))
    )
    (net (code "32") (name "GPA3") (class "Default")
      (node (ref "IC1") (pin "24") (pinfunction "GPA3_24") (pintype "bidirectional"))
      (node (ref "IL4") (pin "A") (pinfunction "A_A") (pintype "passive"))
      (node (ref "IR1") (pin "1") (pinfunction "1_1") (pintype "passive"))
      (node (ref "OK1") (pin "9") (pinfunction "EMIT_9") (pintype "passive"))
    )
    (net (code "33") (name "GPA4") (class "Default")
      (node (ref "IC1") (pin "25") (pinfunction "GPA4_25") (pintype "bidirectional"))
      (node (ref "IL5") (pin "A") (pinfunction "A_A") (pintype "passive"))
      (node (ref "IR2") (pin "4") (pinfunction "1_4") (pintype "passive"))
      (node (ref "OK2") (pin "15") (pinfunction "EMIT_15") (pintype "passive"))
    )
    (net (code "34") (name "GPA5") (class "Default")
      (node (ref "IC1") (pin "26") (pinfunction "GPA5_26") (pintype "bidirectional"))
      (node (ref "IL6") (pin "A") (pinfunction "A_A") (pintype "passive"))
      (node (ref "IR2") (pin "3") (pinfunction "1_3") (pintype "passive"))
      (node (ref "OK2") (pin "13") (pinfunction "EMIT_13") (pintype "passive"))
    )
    (net (code "35") (name "GPA6") (class "Default")
      (node (ref "IC1") (pin "27") (pinfunction "GPA6_27") (pintype "bidirectional"))
      (node (ref "IL7") (pin "A") (pinfunction "A_A") (pintype "passive"))
      (node (ref "IR2") (pin "2") (pinfunction "1_2") (pintype "passive"))
      (node (ref "OK2") (pin "11") (pinfunction "EMIT_11") (pintype "passive"))
    )
    (net (code "36") (name "GPA7") (class "Default")
      (node (ref "IC1") (pin "28") (pinfunction "GPA7_28") (pintype "bidirectional"))
      (node (ref "IL8") (pin "A") (pinfunction "A_A") (pintype "passive"))
      (node (ref "IR2") (pin "1") (pinfunction "1_1") (pintype "passive"))
      (node (ref "OK2") (pin "9") (pinfunction "EMIT_9") (pintype "passive"))
    )
    (net (code "37") (name "GPB0") (class "Default")
      (node (ref "IC1") (pin "1") (pinfunction "GPB0_1") (pintype "bidirectional"))
      (node (ref "OR4") (pin "8") (pinfunction "2_8") (pintype "passive"))
    )
    (net (code "38") (name "GPB1") (class "Default")
      (node (ref "IC1") (pin "2") (pinfunction "GPB1_2") (pintype "bidirectional"))
      (node (ref "OR4") (pin "7") (pinfunction "2_7") (pintype "passive"))
    )
    (net (code "39") (name "GPB2") (class "Default")
      (node (ref "IC1") (pin "3") (pinfunction "GPB2_3") (pintype "bidirectional"))
      (node (ref "OR4") (pin "6") (pinfunction "2_6") (pintype "passive"))
    )
    (net (code "40") (name "GPB3") (class "Default")
      (node (ref "IC1") (pin "4") (pinfunction "GPB3_4") (pintype "bidirectional"))
      (node (ref "OR4") (pin "5") (pinfunction "2_5") (pintype "passive"))
    )
    (net (code "41") (name "GPB4") (class "Default")
      (node (ref "IC1") (pin "5") (pinfunction "GPB4_5") (pintype "bidirectional"))
      (node (ref "OR1") (pin "8") (pinfunction "2_8") (pintype "passive"))
    )
    (net (code "42") (name "GPB5") (class "Default")
      (node (ref "IC1") (pin "6") (pinfunction "GPB5_6") (pintype "bidirectional"))
      (node (ref "OR1") (pin "7") (pinfunction "2_7") (pintype "passive"))
    )
    (net (code "43") (name "GPB6") (class "Default")
      (node (ref "IC1") (pin "7") (pinfunction "GPB6_7") (pintype "bidirectional"))
      (node (ref "OR1") (pin "6") (pinfunction "2_6") (pintype "passive"))
    )
    (net (code "44") (name "GPB7") (class "Default")
      (node (ref "IC1") (pin "8") (pinfunction "GPB7_8") (pintype "bidirectional"))
      (node (ref "OR1") (pin "5") (pinfunction "2_5") (pintype "passive"))
    )
    (net (code "45") (name "IO5") (class "Default")
      (node (ref "OK4") (pin "15") (pinfunction "EMIT_15") (pintype "passive"))
      (node (ref "OR6") (pin "8") (pinfunction "2_8") (pintype "passive"))
      (node (ref "U1") (pin "4") (pinfunction "4B_4") (pintype "input"))
    )
    (net (code "46") (name "IO6") (class "Default")
      (node (ref "OK4") (pin "13") (pinfunction "EMIT_13") (pintype "passive"))
      (node (ref "OR6") (pin "2") (pinfunction "1_2") (pintype "passive"))
      (node (ref "U1") (pin "3") (pinfunction "3B_3") (pintype "input"))
    )
    (net (code "47") (name "IO7") (class "Default")
      (node (ref "OK4") (pin "11") (pinfunction "EMIT_11") (pintype "passive"))
      (node (ref "OR6") (pin "3") (pinfunction "1_3") (pintype "passive"))
      (node (ref "U1") (pin "2") (pinfunction "2B_2") (pintype "input"))
    )
    (net (code "48") (name "IO8") (class "Default")
      (node (ref "OK4") (pin "9") (pinfunction "EMIT_9") (pintype "passive"))
      (node (ref "OR6") (pin "4") (pinfunction "1_4") (pintype "passive"))
      (node (ref "U1") (pin "1") (pinfunction "1B_1") (pintype "input"))
    )
    (net (code "49") (name "LEDA") (class "Default")
      (node (ref "ER3") (pin "1") (pinfunction "1_1") (pintype "passive"))
      (node (ref "U$2") (pin "Y+") (pinfunction "Y+_Y+") (pintype "bidirectional"))
    )
    (net (code "50") (name "LEDB") (class "Default")
      (node (ref "ER4") (pin "1") (pinfunction "1_1") (pintype "passive"))
      (node (ref "U$2") (pin "G+") (pinfunction "G+_G+") (pintype "bidirectional"))
    )
    (net (code "51") (name "Net-(ENC-LEDA)") (class "Default")
      (node (ref "ENC") (pin "27") (pinfunction "LEDA_27") (pintype "output"))
      (node (ref "ER3") (pin "2") (pinfunction "2_2") (pintype "passive"))
    )
    (net (code "52") (name "Net-(ENC-LEDB)") (class "Default")
      (node (ref "ENC") (pin "26") (pinfunction "LEDB_26") (pintype "output"))
      (node (ref "ER4") (pin "2") (pinfunction "2_2") (pintype "passive"))
    )
    (net (code "53") (name "Net-(ENC-OSC1)") (class "Default")
      (node (ref "EC1") (pin "1") (pinfunction "1_1") (pintype "passive"))
      (node (ref "ENC") (pin "23") (pinfunction "OSC1_23") (pintype "input"))
      (node (ref "Q2") (pin "2") (pinfunction "2_2") (pintype "passive"))
    )
    (net (code "54") (name "Net-(ENC-OSC2)") (class "Default")
      (node (ref "EC2") (pin "1") (pinfunction "1_1") (pintype "passive"))
      (node (ref "ENC") (pin "24") (pinfunction "OSC2_24") (pintype "output"))
      (node (ref "Q2") (pin "1") (pinfunction "1_1") (pintype "passive"))
    )
    (net (code "55") (name "Net-(ENC-RBIAS)") (class "Default")
      (node (ref "ENC") (pin "14") (pinfunction "RBIAS_14") (pintype "passive"))
      (node (ref "ER10") (pin "1") (pinfunction "1_1") (pintype "passive"))
    )
    (net (code "56") (name "Net-(ENC-RESET)") (class "Default")
      (node (ref "ENC") (pin "10") (pinfunction "RESET_10") (pintype "input"))
      (node (ref "ER1") (pin "1") (pinfunction "1_1") (pintype "passive"))
    )
    (net (code "57") (name "Net-(ENC-TPIN+)") (class "Default")
      (node (ref "ENC") (pin "13") (pinfunction "TPIN+_13") (pintype "input"))
      (node (ref "ERN1") (pin "6") (pinfunction "2_6") (pintype "passive"))
      (node (ref "U$2") (pin "RD+") (pinfunction "RD+_RD+") (pintype "bidirectional"))
    )
    (net (code "58") (name "Net-(ENC-TPIN-)") (class "Default")
      (node (ref "ENC") (pin "12") (pinfunction "TPIN-_12") (pintype "input"))
      (node (ref "ERN1") (pin "5") (pinfunction "2_5") (pintype "passive"))
      (node (ref "U$2") (pin "RD-") (pinfunction "RD-_RD-") (pintype "bidirectional"))
    )
    (net (code "59") (name "Net-(ENC-TPOUT+)") (class "Default")
      (node (ref "ENC") (pin "17") (pinfunction "TPOUT+_17") (pintype "output"))
      (node (ref "ERN1") (pin "1") (pinfunction "1_1") (pintype "passive"))
      (node (ref "U$2") (pin "TD+") (pinfunction "TD+_TD+") (pintype "bidirectional"))
    )
    (net (code "60") (name "Net-(ENC-TPOUT-)") (class "Default")
      (node (ref "ENC") (pin "16") (pinfunction "TPOUT-_16") (pintype "output"))
      (node (ref "ERN1") (pin "2") (pinfunction "1_2") (pintype "passive"))
      (node (ref "U$2") (pin "TD-") (pinfunction "TD-_TD-") (pintype "bidirectional"))
    )
    (net (code "61") (name "Net-(ENC-VCAP)") (class "Default")
      (node (ref "EC3") (pin "+") (pinfunction "+_+") (pintype "passive"))
      (node (ref "ENC") (pin "1") (pinfunction "VCAP_1") (pintype "power_in"))
    )
    (net (code "62") (name "Net-(ERN1A-2)") (class "Default")
      (node (ref "EC4") (pin "1") (pinfunction "1_1") (pintype "passive"))
      (node (ref "EL1") (pin "2") (pinfunction "2_2") (pintype "passive"))
      (node (ref "ERN1") (pin "7") (pinfunction "2_7") (pintype "passive"))
      (node (ref "ERN1") (pin "8") (pinfunction "2_8") (pintype "passive"))
      (node (ref "U$2") (pin "P4") (pinfunction "P4_P4") (pintype "bidirectional"))
    )
    (net (code "63") (name "Net-(ERN1C-1)") (class "Default")
      (node (ref "EC5") (pin "1") (pinfunction "1_1") (pintype "passive"))
      (node (ref "ERN1") (pin "3") (pinfunction "1_3") (pintype "passive"))
      (node (ref "ERN1") (pin "4") (pinfunction "1_4") (pintype "passive"))
      (node (ref "U$2") (pin "P5") (pinfunction "P5_P5") (pintype "bidirectional"))
    )
    (net (code "64") (name "Net-(IC1-A0)") (class "Default")
      (node (ref "IC1") (pin "15") (pinfunction "A0_15") (pintype "input"))
      (node (ref "MR3") (pin "1") (pinfunction "1_1") (pintype "passive"))
    )
    (net (code "65") (name "Net-(IIR1A-2)") (class "Default")
      (node (ref "IIR1") (pin "8") (pinfunction "2_8") (pintype "passive"))
      (node (ref "OK1") (pin "1") (pinfunction "A_1") (pintype "passive"))
    )
    (net (code "66") (name "Net-(IIR1B-1)") (class "Default")
      (node (ref "IIR1") (pin "2") (pinfunction "1_2") (pintype "passive"))
      (node (ref "XI1") (pin "3") (pinfunction "SK_3") (pintype "passive"))
    )
    (net (code "67") (name "Net-(IIR1B-2)") (class "Default")
      (node (ref "IIR1") (pin "7") (pinfunction "2_7") (pintype "passive"))
      (node (ref "OK1") (pin "3") (pinfunction "A_3") (pintype "passive"))
    )
    (net (code "68") (name "Net-(IIR1C-1)") (class "Default")
      (node (ref "IIR1") (pin "3") (pinfunction "1_3") (pintype "passive"))
      (node (ref "XI1") (pin "4") (pinfunction "SK_4") (pintype "passive"))
    )
    (net (code "69") (name "Net-(IIR1C-2)") (class "Default")
      (node (ref "IIR1") (pin "6") (pinfunction "2_6") (pintype "passive"))
      (node (ref "OK1") (pin "5") (pinfunction "A_5") (pintype "passive"))
    )
    (net (code "70") (name "Net-(IIR1D-1)") (class "Default")
      (node (ref "IIR1") (pin "4") (pinfunction "1_4") (pintype "passive"))
      (node (ref "XI1") (pin "5") (pinfunction "SK_5") (pintype "passive"))
    )
    (net (code "71") (name "Net-(IIR1D-2)") (class "Default")
      (node (ref "IIR1") (pin "5") (pinfunction "2_5") (pintype "passive"))
      (node (ref "OK1") (pin "7") (pinfunction "A_7") (pintype "passive"))
    )
    (net (code "72") (name "Net-(IIR2A-2)") (class "Default")
      (node (ref "IIR2") (pin "8") (pinfunction "2_8") (pintype "passive"))
      (node (ref "OK2") (pin "1") (pinfunction "A_1") (pintype "passive"))
    )
    (net (code "73") (name "Net-(IIR2B-1)") (class "Default")
      (node (ref "IIR2") (pin "2") (pinfunction "1_2") (pintype "passive"))
      (node (ref "XI2") (pin "3") (pinfunction "SK_3") (pintype "passive"))
    )
    (net (code "74") (name "Net-(IIR2B-2)") (class "Default")
      (node (ref "IIR2") (pin "7") (pinfunction "2_7") (pintype "passive"))
      (node (ref "OK2") (pin "3") (pinfunction "A_3") (pintype "passive"))
    )
    (net (code "75") (name "Net-(IIR2C-1)") (class "Default")
      (node (ref "IIR2") (pin "3") (pinfunction "1_3") (pintype "passive"))
      (node (ref "XI2") (pin "4") (pinfunction "SK_4") (pintype "passive"))
    )
    (net (code "76") (name "Net-(IIR2C-2)") (class "Default")
      (node (ref "IIR2") (pin "6") (pinfunction "2_6") (pintype "passive"))
      (node (ref "OK2") (pin "5") (pinfunction "A_5") (pintype "passive"))
    )
    (net (code "77") (name "Net-(IIR2D-1)") (class "Default")
      (node (ref "IIR2") (pin "4") (pinfunction "1_4") (pintype "passive"))
      (node (ref "XI2") (pin "5") (pinfunction "SK_5") (pintype "passive"))
    )
    (net (code "78") (name "Net-(IIR2D-2)") (class "Default")
      (node (ref "IIR2") (pin "5") (pinfunction "2_5") (pintype "passive"))
      (node (ref "OK2") (pin "7") (pinfunction "A_7") (pintype "passive"))
    )
    (net (code "79") (name "Net-(INDL-PadA)") (class "Default")
      (node (ref "INDL") (pin "A") (pinfunction "A_A") (pintype "passive"))
      (node (ref "R6") (pin "2") (pinfunction "2_2") (pintype "passive"))
    )
    (net (code "80") (name "Net-(IR3A-2)") (class "Default")
      (node (ref "IL1") (pin "C") (pinfunction "C_C") (pintype "passive"))
      (node (ref "IR3") (pin "8") (pinfunction "2_8") (pintype "passive"))
    )
    (net (code "81") (name "Net-(IR3B-2)") (class "Default")
      (node (ref "IL2") (pin "C") (pinfunction "C_C") (pintype "passive"))
      (node (ref "IR3") (pin "7") (pinfunction "2_7") (pintype "passive"))
    )
    (net (code "82") (name "Net-(IR3C-2)") (class "Default")
      (node (ref "IL3") (pin "C") (pinfunction "C_C") (pintype "passive"))
      (node (ref "IR3") (pin "6") (pinfunction "2_6") (pintype "passive"))
    )
    (net (code "83") (name "Net-(IR3D-2)") (class "Default")
      (node (ref "IL4") (pin "C") (pinfunction "C_C") (pintype "passive"))
      (node (ref "IR3") (pin "5") (pinfunction "2_5") (pintype "passive"))
    )
    (net (code "84") (name "Net-(IR4A-2)") (class "Default")
      (node (ref "IL5") (pin "C") (pinfunction "C_C") (pintype "passive"))
      (node (ref "IR4") (pin "8") (pinfunction "2_8") (pintype "passive"))
    )
    (net (code "85") (name "Net-(IR4B-2)") (class "Default")
      (node (ref "IL6") (pin "C") (pinfunction "C_C") (pintype "passive"))
      (node (ref "IR4") (pin "7") (pinfunction "2_7") (pintype "passive"))
    )
    (net (code "86") (name "Net-(IR4C-2)") (class "Default")
      (node (ref "IL7") (pin "C") (pinfunction "C_C") (pintype "passive"))
      (node (ref "IR4") (pin "6") (pinfunction "2_6") (pintype "passive"))
    )
    (net (code "87") (name "Net-(IR4D-2)") (class "Default")
      (node (ref "IL8") (pin "C") (pinfunction "C_C") (pintype "passive"))
      (node (ref "IR4") (pin "5") (pinfunction "2_5") (pintype "passive"))
    )
    (net (code "88") (name "Net-(MC-PB6(XTAL1{slash}TOSC1))") (class "Default")
      (node (ref "MC") (pin "7") (pinfunction "PB6(XTAL1/TOSC1)_7") (pintype "bidirectional"))
      (node (ref "Q1") (pin "1") (pinfunction "1_1") (pintype "passive"))
    )
    (net (code "89") (name "Net-(MC-PB7(XTAL2{slash}TOSC2))") (class "Default")
      (node (ref "MC") (pin "8") (pinfunction "PB7(XTAL2/TOSC2)_8") (pintype "bidirectional"))
      (node (ref "Q1") (pin "3") (pinfunction "3_3") (pintype "passive"))
    )
    (net (code "90") (name "Net-(OD1-PadC)") (class "Default")
      (node (ref "OD1") (pin "C") (pinfunction "C_C") (pintype "passive"))
      (node (ref "OMF") (pin "2") (pinfunction "2_2") (pintype "bidirectional"))
    )
    (net (code "91") (name "Net-(OK3A-A)") (class "Default")
      (node (ref "OK3") (pin "1") (pinfunction "A_1") (pintype "passive"))
      (node (ref "OR1") (pin "4") (pinfunction "1_4") (pintype "passive"))
    )
    (net (code "92") (name "Net-(OK3A-C)") (class "Default")
      (node (ref "OK3") (pin "2") (pinfunction "C_2") (pintype "passive"))
      (node (ref "OL1") (pin "A") (pinfunction "A_A") (pintype "passive"))
    )
    (net (code "93") (name "Net-(OK3A-COL)") (class "Default")
      (node (ref "OK3") (pin "16") (pinfunction "COL_16") (pintype "passive"))
      (node (ref "OR3") (pin "1") (pinfunction "1_1") (pintype "passive"))
    )
    (net (code "94") (name "Net-(OK3B-A)") (class "Default")
      (node (ref "OK3") (pin "3") (pinfunction "A_3") (pintype "passive"))
      (node (ref "OR1") (pin "3") (pinfunction "1_3") (pintype "passive"))
    )
    (net (code "95") (name "Net-(OK3B-C)") (class "Default")
      (node (ref "OK3") (pin "4") (pinfunction "C_4") (pintype "passive"))
      (node (ref "OL2") (pin "A") (pinfunction "A_A") (pintype "passive"))
    )
    (net (code "96") (name "Net-(OK3B-COL)") (class "Default")
      (node (ref "OK3") (pin "14") (pinfunction "COL_14") (pintype "passive"))
      (node (ref "OR3") (pin "2") (pinfunction "1_2") (pintype "passive"))
    )
    (net (code "97") (name "Net-(OK3C-A)") (class "Default")
      (node (ref "OK3") (pin "5") (pinfunction "A_5") (pintype "passive"))
      (node (ref "OR1") (pin "2") (pinfunction "1_2") (pintype "passive"))
    )
    (net (code "98") (name "Net-(OK3C-C)") (class "Default")
      (node (ref "OK3") (pin "6") (pinfunction "C_6") (pintype "passive"))
      (node (ref "OL3") (pin "A") (pinfunction "A_A") (pintype "passive"))
    )
    (net (code "99") (name "Net-(OK3C-COL)") (class "Default")
      (node (ref "OK3") (pin "12") (pinfunction "COL_12") (pintype "passive"))
      (node (ref "OR3") (pin "3") (pinfunction "1_3") (pintype "passive"))
    )
    (net (code "100") (name "Net-(OK3D-A)") (class "Default")
      (node (ref "OK3") (pin "7") (pinfunction "A_7") (pintype "passive"))
      (node (ref "OR1") (pin "1") (pinfunction "1_1") (pintype "passive"))
    )
    (net (code "101") (name "Net-(OK3D-C)") (class "Default")
      (node (ref "OK3") (pin "8") (pinfunction "C_8") (pintype "passive"))
      (node (ref "OL4") (pin "A") (pinfunction "A_A") (pintype "passive"))
    )
    (net (code "102") (name "Net-(OK3D-COL)") (class "Default")
      (node (ref "OK3") (pin "10") (pinfunction "COL_10") (pintype "passive"))
      (node (ref "OR3") (pin "4") (pinfunction "1_4") (pintype "passive"))
    )
    (net (code "103") (name "Net-(OK4A-A)") (class "Default")
      (node (ref "OK4") (pin "1") (pinfunction "A_1") (pintype "passive"))
      (node (ref "OR4") (pin "4") (pinfunction "1_4") (pintype "passive"))
    )
    (net (code "104") (name "Net-(OK4A-C)") (class "Default")
      (node (ref "OK4") (pin "2") (pinfunction "C_2") (pintype "passive"))
      (node (ref "OL5") (pin "A") (pinfunction "A_A") (pintype "passive"))
    )
    (net (code "105") (name "Net-(OK4A-COL)") (class "Default")
      (node (ref "OK4") (pin "16") (pinfunction "COL_16") (pintype "passive"))
      (node (ref "OR5") (pin "1") (pinfunction "1_1") (pintype "passive"))
    )
    (net (code "106") (name "Net-(OK4B-A)") (class "Default")
      (node (ref "OK4") (pin "3") (pinfunction "A_3") (pintype "passive"))
      (node (ref "OR4") (pin "3") (pinfunction "1_3") (pintype "passive"))
    )
    (net (code "107") (name "Net-(OK4B-C)") (class "Default")
      (node (ref "OK4") (pin "4") (pinfunction "C_4") (pintype "passive"))
      (node (ref "OL6") (pin "A") (pinfunction "A_A") (pintype "passive"))
    )
    (net (code "108") (name "Net-(OK4B-COL)") (class "Default")
      (node (ref "OK4") (pin "14") (pinfunction "COL_14") (pintype "passive"))
      (node (ref "OR5") (pin "2") (pinfunction "1_2") (pintype "passive"))
    )
    (net (code "109") (name "Net-(OK4C-A)") (class "Default")
      (node (ref "OK4") (pin "5") (pinfunction "A_5") (pintype "passive"))
      (node (ref "OR4") (pin "2") (pinfunction "1_2") (pintype "passive"))
    )
    (net (code "110") (name "Net-(OK4C-C)") (class "Default")
      (node (ref "OK4") (pin "6") (pinfunction "C_6") (pintype "passive"))
      (node (ref "OL7") (pin "A") (pinfunction "A_A") (pintype "passive"))
    )
    (net (code "111") (name "Net-(OK4C-COL)") (class "Default")
      (node (ref "OK4") (pin "12") (pinfunction "COL_12") (pintype "passive"))
      (node (ref "OR5") (pin "3") (pinfunction "1_3") (pintype "passive"))
    )
    (net (code "112") (name "Net-(OK4D-A)") (class "Default")
      (node (ref "OK4") (pin "7") (pinfunction "A_7") (pintype "passive"))
      (node (ref "OR4") (pin "1") (pinfunction "1_1") (pintype "passive"))
    )
    (net (code "113") (name "Net-(OK4D-C)") (class "Default")
      (node (ref "OK4") (pin "8") (pinfunction "C_8") (pintype "passive"))
      (node (ref "OL8") (pin "A") (pinfunction "A_A") (pintype "passive"))
    )
    (net (code "114") (name "Net-(OK4D-COL)") (class "Default")
      (node (ref "OK4") (pin "10") (pinfunction "COL_10") (pintype "passive"))
      (node (ref "OR5") (pin "4") (pinfunction "1_4") (pintype "passive"))
    )
    (net (code "115") (name "Net-(PD1-PadC)") (class "Default")
      (node (ref "PD1") (pin "C") (pinfunction "C_C") (pintype "passive"))
      (node (ref "PF1") (pin "1") (pinfunction "1_1") (pintype "passive"))
    )
    (net (code "116") (name "Net-(PIC33-OUT)") (class "Default")
      (node (ref "PCO") (pin "P$2") (pinfunction "P$2_P$2") (pintype "passive"))
      (node (ref "PD2") (pin "C") (pinfunction "C_C") (pintype "passive"))
      (node (ref "PIC33") (pin "2") (pinfunction "OUT_2") (pintype "output"))
    )
    (net (code "117") (name "Net-(PL-PadA)") (class "Default")
      (node (ref "PL") (pin "A") (pinfunction "A_A") (pintype "passive"))
      (node (ref "PR1") (pin "1") (pinfunction "1_1") (pintype "passive"))
    )
    (net (code "118") (name "Net-(U1-1C)") (class "Default")
      (node (ref "D1") (pin "2") (pinfunction "2_2") (pintype "bidirectional"))
      (node (ref "OF8") (pin "2") (pinfunction "2_2") (pintype "bidirectional"))
      (node (ref "U1") (pin "18") (pinfunction "1C_18") (pintype "output"))
    )
    (net (code "119") (name "Net-(U1-2C)") (class "Default")
      (node (ref "D1") (pin "1") (pinfunction "1_1") (pintype "bidirectional"))
      (node (ref "OF7") (pin "2") (pinfunction "2_2") (pintype "bidirectional"))
      (node (ref "U1") (pin "17") (pinfunction "2C_17") (pintype "output"))
    )
    (net (code "120") (name "Net-(U1-3C)") (class "Default")
      (node (ref "D2") (pin "2") (pinfunction "2_2") (pintype "bidirectional"))
      (node (ref "OF6") (pin "2") (pinfunction "2_2") (pintype "bidirectional"))
      (node (ref "U1") (pin "16") (pinfunction "3C_16") (pintype "output"))
    )
    (net (code "121") (name "Net-(U1-4C)") (class "Default")
      (node (ref "D2") (pin "1") (pinfunction "1_1") (pintype "bidirectional"))
      (node (ref "OF5") (pin "2") (pinfunction "2_2") (pintype "bidirectional"))
      (node (ref "U1") (pin "15") (pinfunction "4C_15") (pintype "output"))
    )
    (net (code "122") (name "Net-(U1-5C)") (class "Default")
      (node (ref "D3") (pin "2") (pinfunction "2_2") (pintype "bidirectional"))
      (node (ref "OF4") (pin "2") (pinfunction "2_2") (pintype "bidirectional"))
      (node (ref "U1") (pin "14") (pinfunction "5C_14") (pintype "output"))
    )
    (net (code "123") (name "Net-(U1-6C)") (class "Default")
      (node (ref "D3") (pin "1") (pinfunction "1_1") (pintype "bidirectional"))
      (node (ref "OF3") (pin "2") (pinfunction "2_2") (pintype "bidirectional"))
      (node (ref "U1") (pin "13") (pinfunction "6C_13") (pintype "output"))
    )
    (net (code "124") (name "Net-(U1-7C)") (class "Default")
      (node (ref "D4") (pin "2") (pinfunction "2_2") (pintype "bidirectional"))
      (node (ref "OF2") (pin "2") (pinfunction "2_2") (pintype "bidirectional"))
      (node (ref "U1") (pin "12") (pinfunction "7C_12") (pintype "output"))
    )
    (net (code "125") (name "Net-(U1-8C)") (class "Default")
      (node (ref "D4") (pin "1") (pinfunction "1_1") (pintype "bidirectional"))
      (node (ref "OF1") (pin "2") (pinfunction "2_2") (pintype "bidirectional"))
      (node (ref "U1") (pin "11") (pinfunction "8C_11") (pintype "output"))
    )
    (net (code "126") (name "Net-(XI1B-SK)") (class "Default")
      (node (ref "IIR1") (pin "1") (pinfunction "1_1") (pintype "passive"))
      (node (ref "XI1") (pin "2") (pinfunction "SK_2") (pintype "passive"))
    )
    (net (code "127") (name "Net-(XI2B-SK)") (class "Default")
      (node (ref "IIR2") (pin "1") (pinfunction "1_1") (pintype "passive"))
      (node (ref "XI2") (pin "2") (pinfunction "SK_2") (pintype "passive"))
    )
    (net (code "128") (name "Net-(XOA-SK)") (class "Default")
      (node (ref "OD1") (pin "A") (pinfunction "A_A") (pintype "passive"))
      (node (ref "XO") (pin "1") (pinfunction "SK_1") (pintype "passive"))
    )
    (net (code "129") (name "Net-(XOB-SK)") (class "Default")
      (node (ref "OF8") (pin "1") (pinfunction "1_1") (pintype "bidirectional"))
      (node (ref "XO") (pin "10") (pinfunction "SK_10") (pintype "passive"))
    )
    (net (code "130") (name "Net-(XOD-SK)") (class "Default")
      (node (ref "OF1") (pin "1") (pinfunction "1_1") (pintype "bidirectional"))
      (node (ref "XO") (pin "3") (pinfunction "SK_3") (pintype "passive"))
    )
    (net (code "131") (name "Net-(XOE-SK)") (class "Default")
      (node (ref "OF2") (pin "1") (pinfunction "1_1") (pintype "bidirectional"))
      (node (ref "XO") (pin "4") (pinfunction "SK_4") (pintype "passive"))
    )
    (net (code "132") (name "Net-(XOF-SK)") (class "Default")
      (node (ref "OF3") (pin "1") (pinfunction "1_1") (pintype "bidirectional"))
      (node (ref "XO") (pin "5") (pinfunction "SK_5") (pintype "passive"))
    )
    (net (code "133") (name "Net-(XOG-SK)") (class "Default")
      (node (ref "OF4") (pin "1") (pinfunction "1_1") (pintype "bidirectional"))
      (node (ref "XO") (pin "6") (pinfunction "SK_6") (pintype "passive"))
    )
    (net (code "134") (name "Net-(XOH-SK)") (class "Default")
      (node (ref "OF5") (pin "1") (pinfunction "1_1") (pintype "bidirectional"))
      (node (ref "XO") (pin "7") (pinfunction "SK_7") (pintype "passive"))
    )
    (net (code "135") (name "Net-(XOI-SK)") (class "Default")
      (node (ref "OF6") (pin "1") (pinfunction "1_1") (pintype "bidirectional"))
      (node (ref "XO") (pin "8") (pinfunction "SK_8") (pintype "passive"))
    )
    (net (code "136") (name "Net-(XOJ-SK)") (class "Default")
      (node (ref "OF7") (pin "1") (pinfunction "1_1") (pintype "bidirectional"))
      (node (ref "XO") (pin "9") (pinfunction "SK_9") (pintype "passive"))
    )
    (net (code "137") (name "OI1") (class "Default")
      (node (ref "OK3") (pin "15") (pinfunction "EMIT_15") (pintype "passive"))
      (node (ref "OR2") (pin "1") (pinfunction "1_1") (pintype "passive"))
      (node (ref "U1") (pin "8") (pinfunction "8B_8") (pintype "input"))
    )
    (net (code "138") (name "OI2") (class "Default")
      (node (ref "OK3") (pin "13") (pinfunction "EMIT_13") (pintype "passive"))
      (node (ref "OR2") (pin "2") (pinfunction "1_2") (pintype "passive"))
      (node (ref "U1") (pin "7") (pinfunction "7B_7") (pintype "input"))
    )
    (net (code "139") (name "OI3") (class "Default")
      (node (ref "OK3") (pin "11") (pinfunction "EMIT_11") (pintype "passive"))
      (node (ref "OR2") (pin "3") (pinfunction "1_3") (pintype "passive"))
      (node (ref "U1") (pin "6") (pinfunction "6B_6") (pintype "input"))
    )
    (net (code "140") (name "OI4") (class "Default")
      (node (ref "OK3") (pin "9") (pinfunction "EMIT_9") (pintype "passive"))
      (node (ref "OR2") (pin "4") (pinfunction "1_4") (pintype "passive"))
      (node (ref "U1") (pin "5") (pinfunction "5B_5") (pintype "input"))
    )
    (net (code "141") (name "RAW_IV") (class "Default")
      (node (ref "GPIO") (pin "1") (pinfunction "S_1") (pintype "passive"))
      (node (ref "PC1") (pin "+") (pinfunction "+_+") (pintype "passive"))
      (node (ref "PF1") (pin "2") (pinfunction "2_2") (pintype "passive"))
      (node (ref "PIC33") (pin "1") (pinfunction "VIN_1") (pintype "input"))
    )
    (net (code "142") (name "RESET") (class "Default")
      (node (ref "BL") (pin "5") (pinfunction "S_5") (pintype "passive"))
      (node (ref "C2") (pin "1") (pinfunction "1_1") (pintype "passive"))
      (node (ref "MC") (pin "29") (pinfunction "PC6(/RESET)_29") (pintype "bidirectional"))
      (node (ref "R2") (pin "1") (pinfunction "1_1") (pintype "passive"))
      (node (ref "SR") (pin "1") (pinfunction "P_1") (pintype "passive"))
    )
    (net (code "143") (name "RXI") (class "Default")
      (node (ref "MC") (pin "30") (pinfunction "PD0(RXD)_30") (pintype "bidirectional"))
      (node (ref "PP") (pin "4") (pinfunction "S_4") (pintype "passive"))
    )
    (net (code "144") (name "TXO") (class "Default")
      (node (ref "MC") (pin "31") (pinfunction "PD1(TXD)_31") (pintype "bidirectional"))
      (node (ref "PP") (pin "3") (pinfunction "S_3") (pintype "passive"))
    )
    (net (code "145") (name "VDDO") (class "Default")
      (node (ref "D1") (pin "3") (pinfunction "3_3") (pintype "bidirectional"))
      (node (ref "D2") (pin "3") (pinfunction "3_3") (pintype "bidirectional"))
      (node (ref "D3") (pin "3") (pinfunction "3_3") (pintype "bidirectional"))
      (node (ref "D4") (pin "3") (pinfunction "3_3") (pintype "bidirectional"))
      (node (ref "EC6") (pin "+") (pinfunction "+_+") (pintype "passive"))
      (node (ref "OD2") (pin "C") (pinfunction "C_C") (pintype "passive"))
      (node (ref "OMF") (pin "1") (pinfunction "1_1") (pintype "bidirectional"))
      (node (ref "OR3") (pin "5") (pinfunction "2_5") (pintype "passive"))
      (node (ref "OR3") (pin "6") (pinfunction "2_6") (pintype "passive"))
      (node (ref "OR3") (pin "7") (pinfunction "2_7") (pintype "passive"))
      (node (ref "OR3") (pin "8") (pinfunction "2_8") (pintype "passive"))
      (node (ref "OR5") (pin "5") (pinfunction "2_5") (pintype "passive"))
      (node (ref "OR5") (pin "6") (pinfunction "2_6") (pintype "passive"))
      (node (ref "OR5") (pin "7") (pinfunction "2_7") (pintype "passive"))
      (node (ref "OR5") (pin "8") (pinfunction "2_8") (pintype "passive"))
      (node (ref "U1") (pin "10") (pinfunction "COM_10") (pintype "output"))
    )
    (net (code "146") (name "VIN") (class "Default")
      (node (ref "PD1") (pin "A") (pinfunction "A_A") (pintype "passive"))
      (node (ref "PJ1") (pin "VIN0") (pinfunction "PWR_VIN0") (pintype "bidirectional"))
      (node (ref "XV") (pin "2") (pinfunction "SK_2") (pintype "passive"))
    )
    (net (code "147") (name "WFGPIO0") (class "Default")
      (node (ref "GPIO") (pin "13") (pinfunction "S_13") (pintype "passive"))
      (node (ref "WIFI") (pin "GPIO0") (pinfunction "GPIO0_GPIO0") (pintype "bidirectional"))
    )
    (net (code "148") (name "WFGPIO2") (class "Default")
      (node (ref "GPIO") (pin "14") (pinfunction "S_14") (pintype "passive"))
      (node (ref "WIFI") (pin "GPIO2") (pinfunction "GPIO2_GPIO2") (pintype "bidirectional"))
    )
    (net (code "149") (name "unconnected-(ENC-CLKOUT-Pad3)") (class "Default")
      (node (ref "ENC") (pin "3") (pinfunction "CLKOUT_3") (pintype "output"))
    )
    (net (code "150") (name "unconnected-(ENC-WOL-Pad5)") (class "Default")
      (node (ref "ENC") (pin "5") (pinfunction "WOL_5") (pintype "output"))
    )
    (net (code "151") (name "unconnected-(IC1-INTA-Pad20)") (class "Default")
      (node (ref "IC1") (pin "20") (pinfunction "INTA_20") (pintype "output"))
    )
    (net (code "152") (name "unconnected-(PJ1-GND-PadP$4)") (class "Default")
      (node (ref "PJ1") (pin "P$4") (pinfunction "GND_P$4") (pintype "bidirectional"))
    )
    (net (code "153") (name "unconnected-(U$2-PadNC)") (class "Default")
      (node (ref "U$2") (pin "NC") (pinfunction "NC_NC") (pintype "bidirectional"))
    )
    (net (code "154") (name "unconnected-(WIFI-PadRST)") (class "Default")
      (node (ref "WIFI") (pin "RST") (pinfunction "RST_RST") (pintype "bidirectional"))
    )
  )
)
